# preamp-buffer-supreme_v1_0.net
KiCad netlist of a schematic drawn in EAGLE
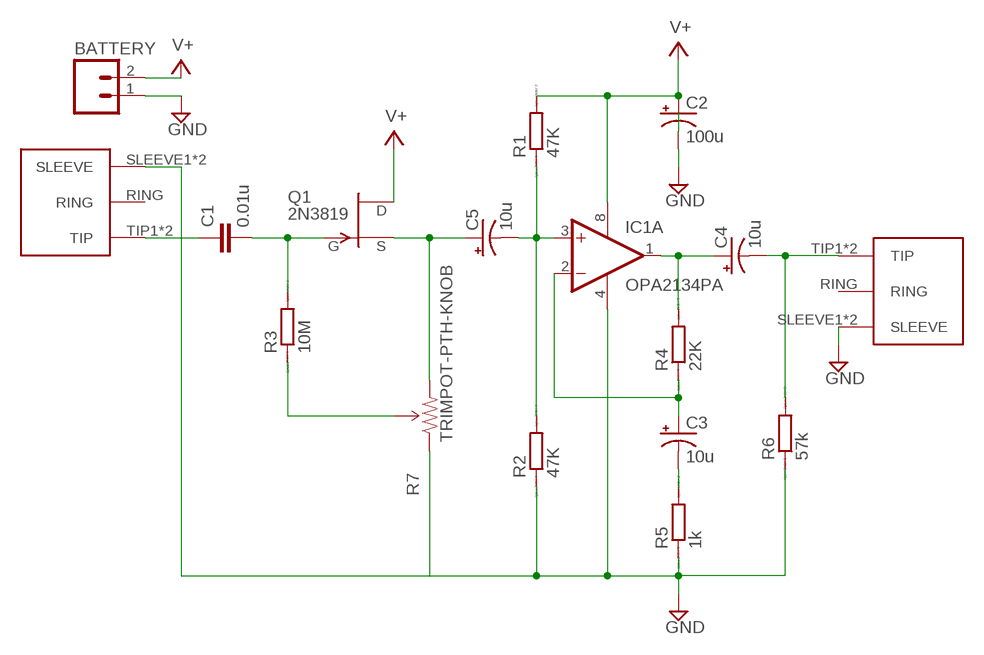
[diagram p0: schematic, sheet 1]

(export (version "E")
  (design (tool "Eeschema 10.0.6"))
  (components
    (comp (ref "BATTERY")
      (value "M02PTH")
      (footprint "eagle-import:1X02")
      (libsource (lib "eagle-import") (part "M02PTH"))
    )
    (comp (ref "C1")
      (value "0.01u")
      (footprint "eagle-import:C5B3")
      (libsource (lib "eagle-import") (part "C5/3"))
    )
    (comp (ref "C2")
      (value "100u")
      (footprint "eagle-import:CPOL-RADIAL-10UF-25V")
      (libsource (lib "eagle-import") (part "CAP_POLPTH2"))
    )
    (comp (ref "C3")
      (value "10u")
      (footprint "eagle-import:CPOL-RADIAL-10UF-25V")
      (libsource (lib "eagle-import") (part "CAP_POLPTH2"))
    )
    (comp (ref "C4")
      (value "10u")
      (footprint "eagle-import:CPOL-RADIAL-10UF-25V")
      (libsource (lib "eagle-import") (part "CAP_POLPTH2"))
    )
    (comp (ref "C5")
      (value "10u")
      (footprint "eagle-import:CPOL-RADIAL-10UF-25V")
      (libsource (lib "eagle-import") (part "CAP_POLPTH2"))
    )
    (comp (ref "IC1")
      (value "OPA2134PA")
      (footprint "eagle-import:DIL08")
      (libsource (lib "eagle-import") (part "OPA2PA134"))
    )
    (comp (ref "Q1")
      (value "2N3819")
      (footprint "eagle-import:TO92")
      (libsource (lib "eagle-import") (part "2N3819"))
    )
    (comp (ref "R1")
      (value "47K")
      (footprint "eagle-import:0204_7")
      (libsource (lib "eagle-import") (part "R0204/7"))
    )
    (comp (ref "R2")
      (value "47K")
      (footprint "eagle-import:0204_7")
      (libsource (lib "eagle-import") (part "R0204/7"))
    )
    (comp (ref "R3")
      (value "10M")
      (footprint "eagle-import:0204_7")
      (libsource (lib "eagle-import") (part "R0204/7"))
    )
    (comp (ref "R4")
      (value "22K")
      (footprint "eagle-import:0204_7")
      (libsource (lib "eagle-import") (part "R0204/7"))
    )
    (comp (ref "R5")
      (value "1k")
      (footprint "eagle-import:0204_7")
      (libsource (lib "eagle-import") (part "R0204/7"))
    )
    (comp (ref "R6")
      (value "57k")
      (footprint "eagle-import:0204_7")
      (libsource (lib "eagle-import") (part "R0204/7"))
    )
    (comp (ref "R7")
      (value "TRIMPOT-PTH-KNOB")
      (footprint "eagle-import:3386U")
      (libsource (lib "eagle-import") (part "TRIMPOT-PTH-KNOB"))
    )
    (comp (ref "U$2")
      (value "3.5MM-STEREO-JACK")
      (footprint "eagle-import:3.5MM-STEREO-JACK")
      (libsource (lib "eagle-import") (part "3.5MM-STEREO-JACK"))
    )
    (comp (ref "U$3")
      (value "3.5MM-STEREO-JACK")
      (footprint "eagle-import:3.5MM-STEREO-JACK")
      (libsource (lib "eagle-import") (part "3.5MM-STEREO-JACK"))
    )
  )
  (nets
    (net (code "1") (name "GND") (class "Default")
      (node (ref "BATTERY") (pin "1") (pinfunction "1_1") (pintype "passive"))
      (node (ref "C2") (pin "2") (pinfunction "-_2") (pintype "passive"))
      (node (ref "IC1") (pin "4") (pinfunction "V-_4") (pintype "power_in"))
      (node (ref "R2") (pin "1") (pinfunction "1_1") (pintype "passive"))
      (node (ref "R5") (pin "1") (pinfunction "1_1") (pintype "passive"))
      (node (ref "R6") (pin "1") (pinfunction "1_1") (pintype "passive"))
      (node (ref "R7") (pin "1") (pinfunction "CCW_1") (pintype "passive"))
      (node (ref "U$2") (pin "SLEEVE1") (pinfunction "SLEEVE_SLEEVE1") (pintype "bidirectional"))
      (node (ref "U$2") (pin "SLEEVE2") (pinfunction "SLEEVE_SLEEVE2") (pintype "bidirectional"))
      (node (ref "U$3") (pin "SLEEVE1") (pinfunction "SLEEVE_SLEEVE1") (pintype "bidirectional"))
      (node (ref "U$3") (pin "SLEEVE2") (pinfunction "SLEEVE_SLEEVE2") (pintype "bidirectional"))
    )
    (net (code "2") (name "Net-(C1-Pad1)") (class "Default")
      (node (ref "C1") (pin "1") (pinfunction "1_1") (pintype "passive"))
      (node (ref "U$2") (pin "TIP1") (pinfunction "TIP_TIP1") (pintype "bidirectional"))
      (node (ref "U$2") (pin "TIP2") (pinfunction "TIP_TIP2") (pintype "bidirectional"))
    )
    (net (code "3") (name "Net-(C3-+)") (class "Default")
      (node (ref "C3") (pin "1") (pinfunction "+_1") (pintype "passive"))
      (node (ref "IC1") (pin "2") (pinfunction "-IN_2") (pintype "input"))
      (node (ref "R4") (pin "1") (pinfunction "1_1") (pintype "passive"))
    )
    (net (code "4") (name "Net-(C3--)") (class "Default")
      (node (ref "C3") (pin "2") (pinfunction "-_2") (pintype "passive"))
      (node (ref "R5") (pin "2") (pinfunction "2_2") (pintype "passive"))
    )
    (net (code "5") (name "Net-(C4-+)") (class "Default")
      (node (ref "C4") (pin "1") (pinfunction "+_1") (pintype "passive"))
      (node (ref "IC1") (pin "1") (pinfunction "OUT_1") (pintype "output"))
      (node (ref "R4") (pin "2") (pinfunction "2_2") (pintype "passive"))
    )
    (net (code "6") (name "Net-(C4--)") (class "Default")
      (node (ref "C4") (pin "2") (pinfunction "-_2") (pintype "passive"))
      (node (ref "R6") (pin "2") (pinfunction "2_2") (pintype "passive"))
      (node (ref "U$3") (pin "TIP1") (pinfunction "TIP_TIP1") (pintype "bidirectional"))
      (node (ref "U$3") (pin "TIP2") (pinfunction "TIP_TIP2") (pintype "bidirectional"))
    )
    (net (code "7") (name "Net-(C5-+)") (class "Default")
      (node (ref "C5") (pin "1") (pinfunction "+_1") (pintype "passive"))
      (node (ref "Q1") (pin "3") (pinfunction "S_3") (pintype "passive"))
      (node (ref "R7") (pin "3") (pinfunction "CW_3") (pintype "passive"))
    )
    (net (code "8") (name "Net-(C5--)") (class "Default")
      (node (ref "C5") (pin "2") (pinfunction "-_2") (pintype "passive"))
      (node (ref "IC1") (pin "3") (pinfunction "+IN_3") (pintype "input"))
      (node (ref "R1") (pin "1") (pinfunction "1_1") (pintype "passive"))
      (node (ref "R2") (pin "2") (pinfunction "2_2") (pintype "passive"))
    )
    (net (code "9") (name "Net-(Q1-G)") (class "Default")
      (node (ref "C1") (pin "2") (pinfunction "2_2") (pintype "passive"))
      (node (ref "Q1") (pin "2") (pinfunction "G_2") (pintype "passive"))
      (node (ref "R3") (pin "2") (pinfunction "2_2") (pintype "passive"))
    )
    (net (code "10") (name "Net-(R7-WIPER)") (class "Default")
      (node (ref "R3") (pin "1") (pinfunction "1_1") (pintype "passive"))
      (node (ref "R7") (pin "2") (pinfunction "WIPER_2") (pintype "passive"))
    )
    (net (code "11") (name "V+") (class "Default")
      (node (ref "BATTERY") (pin "2") (pinfunction "2_2") (pintype "passive"))
      (node (ref "C2") (pin "1") (pinfunction "+_1") (pintype "passive"))
      (node (ref "IC1") (pin "8") (pinfunction "V+_8") (pintype "power_in"))
      (node (ref "Q1") (pin "1") (pinfunction "D_1") (pintype "passive"))
      (node (ref "R1") (pin "2") (pinfunction "2_2") (pintype "passive"))
    )
    (net (code "12") (name "unconnected-(U$2-PadRING)") (class "Default")
      (node (ref "U$2") (pin "RING") (pinfunction "RING_RING") (pintype "bidirectional"))
    )
    (net (code "13") (name "unconnected-(U$3-PadRING)") (class "Default")
      (node (ref "U$3") (pin "RING") (pinfunction "RING_RING") (pintype "bidirectional"))
    )
  )
)
